# hbridge.net
KiCad netlist of a schematic drawn in EAGLE
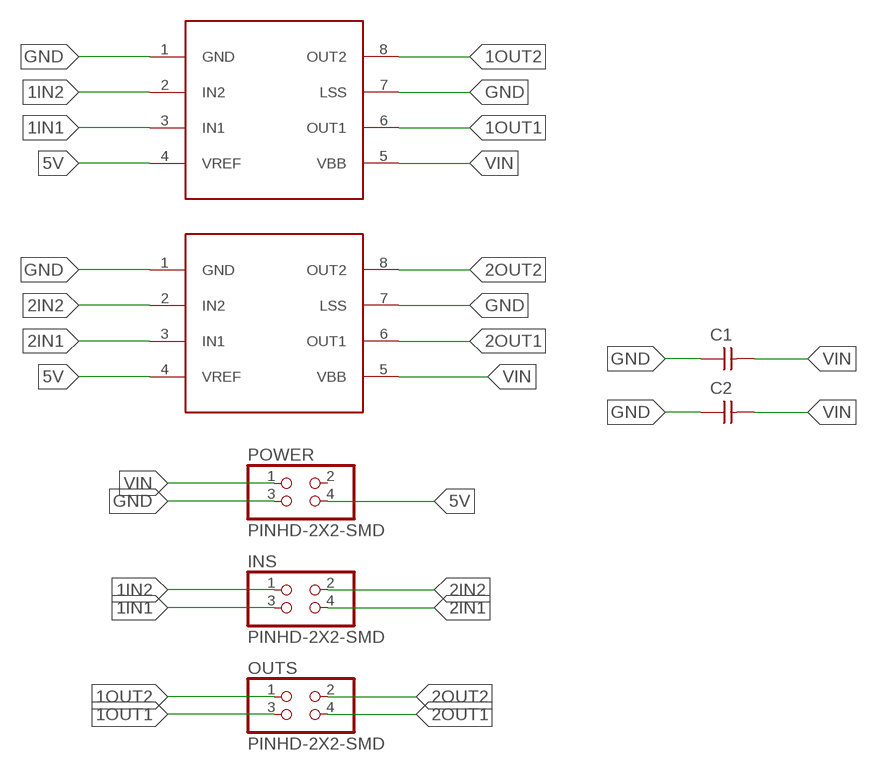
[diagram p0: schematic, sheet 1]

(export (version "E")
  (design (tool "Eeschema 10.0.6"))
  (components
    (comp (ref "C1")
      (value "CAP-UNPOLARIZEDFAB")
      (footprint "eagle-import:C1206FAB")
      (libsource (lib "eagle-import") (part "CAP-UNPOLARIZEDFAB"))
    )
    (comp (ref "C2")
      (value "CAP-UNPOLARIZEDFAB")
      (footprint "eagle-import:C1206FAB")
      (libsource (lib "eagle-import") (part "CAP-UNPOLARIZEDFAB"))
    )
    (comp (ref "INS")
      (value "PINHD-2X2-SMD")
      (footprint "eagle-import:2X02SMD")
      (libsource (lib "eagle-import") (part "PINHD-2X2-SMD"))
    )
    (comp (ref "OUTS")
      (value "PINHD-2X2-SMD")
      (footprint "eagle-import:2X02SMD")
      (libsource (lib "eagle-import") (part "PINHD-2X2-SMD"))
    )
    (comp (ref "POWER")
      (value "PINHD-2X2-SMD")
      (footprint "eagle-import:2X02SMD")
      (libsource (lib "eagle-import") (part "PINHD-2X2-SMD"))
    )
    (comp (ref "U$1")
      (value "A4953-H-BRIDGE-MOTOR-DRIVER")
      (footprint "eagle-import:SOIC8")
      (libsource (lib "eagle-import") (part "A4953-H-BRIDGE-MOTOR-DRIVER"))
    )
    (comp (ref "U$2")
      (value "A4953-H-BRIDGE-MOTOR-DRIVER")
      (footprint "eagle-import:SOIC8")
      (libsource (lib "eagle-import") (part "A4953-H-BRIDGE-MOTOR-DRIVER"))
    )
  )
  (nets
    (net (code "1") (name "1IN1") (class "Default")
      (node (ref "INS") (pin "3") (pinfunction "3_3") (pintype "passive"))
      (node (ref "U$1") (pin "3") (pinfunction "IN1_3") (pintype "bidirectional"))
    )
    (net (code "2") (name "1IN2") (class "Default")
      (node (ref "INS") (pin "1") (pinfunction "1_1") (pintype "passive"))
      (node (ref "U$1") (pin "2") (pinfunction "IN2_2") (pintype "bidirectional"))
    )
    (net (code "3") (name "1OUT1") (class "Default")
      (node (ref "OUTS") (pin "3") (pinfunction "3_3") (pintype "passive"))
      (node (ref "U$1") (pin "6") (pinfunction "OUT1_6") (pintype "bidirectional"))
    )
    (net (code "4") (name "1OUT2") (class "Default")
      (node (ref "OUTS") (pin "1") (pinfunction "1_1") (pintype "passive"))
      (node (ref "U$1") (pin "8") (pinfunction "OUT2_8") (pintype "bidirectional"))
    )
    (net (code "5") (name "2IN1") (class "Default")
      (node (ref "INS") (pin "4") (pinfunction "4_4") (pintype "passive"))
      (node (ref "U$2") (pin "3") (pinfunction "IN1_3") (pintype "bidirectional"))
    )
    (net (code "6") (name "2IN2") (class "Default")
      (node (ref "INS") (pin "2") (pinfunction "2_2") (pintype "passive"))
      (node (ref "U$2") (pin "2") (pinfunction "IN2_2") (pintype "bidirectional"))
    )
    (net (code "7") (name "2OUT1") (class "Default")
      (node (ref "OUTS") (pin "4") (pinfunction "4_4") (pintype "passive"))
      (node (ref "U$2") (pin "6") (pinfunction "OUT1_6") (pintype "bidirectional"))
    )
    (net (code "8") (name "2OUT2") (class "Default")
      (node (ref "OUTS") (pin "2") (pinfunction "2_2") (pintype "passive"))
      (node (ref "U$2") (pin "8") (pinfunction "OUT2_8") (pintype "bidirectional"))
    )
    (net (code "9") (name "5V") (class "Default")
      (node (ref "POWER") (pin "4") (pinfunction "4_4") (pintype "passive"))
      (node (ref "U$1") (pin "4") (pinfunction "VREF_4") (pintype "bidirectional"))
      (node (ref "U$2") (pin "4") (pinfunction "VREF_4") (pintype "bidirectional"))
    )
    (net (code "10") (name "GND") (class "Default")
      (node (ref "C1") (pin "1") (pinfunction "1_1") (pintype "passive"))
      (node (ref "C2") (pin "1") (pinfunction "1_1") (pintype "passive"))
      (node (ref "POWER") (pin "3") (pinfunction "3_3") (pintype "passive"))
      (node (ref "U$1") (pin "1") (pinfunction "GND_1") (pintype "bidirectional"))
      (node (ref "U$1") (pin "7") (pinfunction "LSS_7") (pintype "bidirectional"))
      (node (ref "U$2") (pin "1") (pinfunction "GND_1") (pintype "bidirectional"))
      (node (ref "U$2") (pin "7") (pinfunction "LSS_7") (pintype "bidirectional"))
    )
    (net (code "11") (name "VIN") (class "Default")
      (node (ref "C1") (pin "2") (pinfunction "2_2") (pintype "passive"))
      (node (ref "C2") (pin "2") (pinfunction "2_2") (pintype "passive"))
      (node (ref "POWER") (pin "1") (pinfunction "1_1") (pintype "passive"))
      (node (ref "U$1") (pin "5") (pinfunction "VBB_5") (pintype "bidirectional"))
      (node (ref "U$2") (pin "5") (pinfunction "VBB_5") (pintype "bidirectional"))
    )
    (net (code "12") (name "unconnected-(POWER-Pad2)") (class "Default")
      (node (ref "POWER") (pin "2") (pinfunction "2_2") (pintype "passive"))
    )
  )
)
